# GPS-module.net
KiCad netlist of a schematic drawn in EAGLE
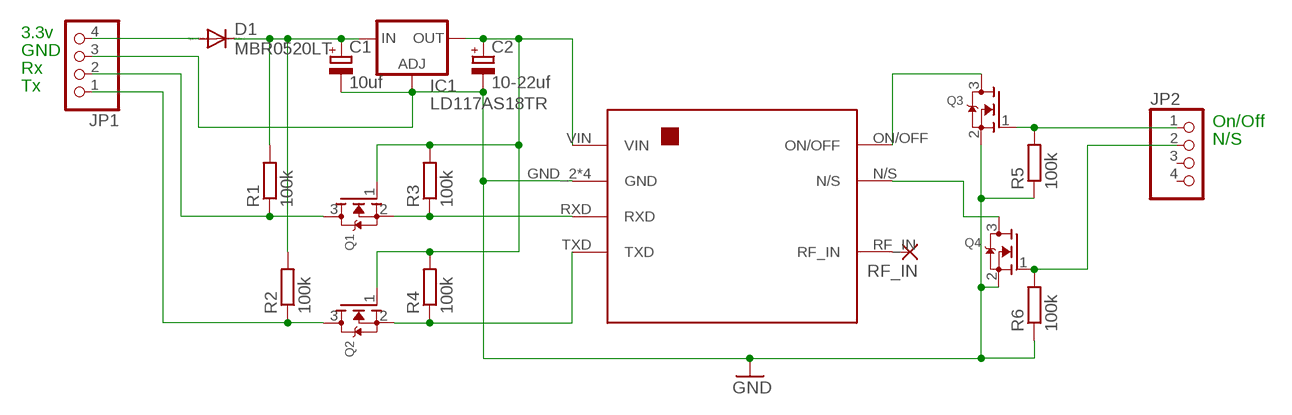
[diagram p0: schematic, sheet 1]

(export (version "E")
  (design (tool "Eeschema 10.0.6"))
  (components
    (comp (ref "C1")
      (value "10uf")
      (footprint "eagle-import:C_6032-28R")
      (libsource (lib "eagle-import") (part "CPOL-EUC/6032-28R"))
    )
    (comp (ref "C2")
      (value "10-22uf")
      (footprint "eagle-import:C_6032-28R")
      (libsource (lib "eagle-import") (part "CPOL-EUC/6032-28R"))
    )
    (comp (ref "D1")
      (value "MBR0520LT")
      (footprint "eagle-import:SOD123")
      (libsource (lib "eagle-import") (part "MBR0520LT"))
    )
    (comp (ref "IC1")
      (value "LD117AS18TR")
      (footprint "eagle-import:SOT223")
      (libsource (lib "eagle-import") (part "LD117A?S18TR"))
    )
    (comp (ref "JP1")
      (value "PINHD-1X4")
      (footprint "eagle-import:1X04")
      (libsource (lib "eagle-import") (part "PINHD-1X4"))
    )
    (comp (ref "JP2")
      (value "PINHD-1X4")
      (footprint "eagle-import:1X04")
      (libsource (lib "eagle-import") (part "PINHD-1X4"))
    )
    (comp (ref "Q1")
      (value "MOSFET-NREFLOW")
      (footprint "eagle-import:SOT23")
      (libsource (lib "eagle-import") (part "MOSFET-NREFLOW"))
    )
    (comp (ref "Q2")
      (value "MOSFET-NREFLOW")
      (footprint "eagle-import:SOT23")
      (libsource (lib "eagle-import") (part "MOSFET-NREFLOW"))
    )
    (comp (ref "Q3")
      (value "MOSFET-NREFLOW")
      (footprint "eagle-import:SOT23")
      (libsource (lib "eagle-import") (part "MOSFET-NREFLOW"))
    )
    (comp (ref "Q4")
      (value "MOSFET-NREFLOW")
      (footprint "eagle-import:SOT23")
      (libsource (lib "eagle-import") (part "MOSFET-NREFLOW"))
    )
    (comp (ref "R1")
      (value "100k")
      (footprint "eagle-import:M0805")
      (libsource (lib "eagle-import") (part "R-EU_M0805"))
    )
    (comp (ref "R2")
      (value "100k")
      (footprint "eagle-import:M0805")
      (libsource (lib "eagle-import") (part "R-EU_M0805"))
    )
    (comp (ref "R3")
      (value "100k")
      (footprint "eagle-import:M0805")
      (libsource (lib "eagle-import") (part "R-EU_M0805"))
    )
    (comp (ref "R4")
      (value "100k")
      (footprint "eagle-import:M0805")
      (libsource (lib "eagle-import") (part "R-EU_M0805"))
    )
    (comp (ref "R5")
      (value "100k")
      (footprint "eagle-import:M0805")
      (libsource (lib "eagle-import") (part "R-EU_M0805"))
    )
    (comp (ref "R6")
      (value "100k")
      (footprint "eagle-import:M0805")
      (libsource (lib "eagle-import") (part "R-EU_M0805"))
    )
    (comp (ref "RF_IN")
      (value "SMD2")
      (footprint "eagle-import:SMD1,27-2,54")
      (libsource (lib "eagle-import") (part "SMD2"))
    )
    (comp (ref "U$1")
      (value "GP4SF1109F2")
      (footprint "eagle-import:GP4SF1109F2")
      (libsource (lib "eagle-import") (part "GP4SF1109F2"))
    )
  )
  (nets
    (net (code "1") (name "GND") (class "Default")
      (node (ref "C1") (pin "-") (pinfunction "-_-") (pintype "passive"))
      (node (ref "C2") (pin "-") (pinfunction "-_-") (pintype "passive"))
      (node (ref "IC1") (pin "1") (pinfunction "ADJ_1") (pintype "input"))
      (node (ref "JP1") (pin "3") (pinfunction "3_3") (pintype "passive"))
      (node (ref "Q3") (pin "2") (pinfunction "S_2") (pintype "bidirectional"))
      (node (ref "Q4") (pin "2") (pinfunction "S_2") (pintype "bidirectional"))
      (node (ref "R5") (pin "1") (pinfunction "1_1") (pintype "passive"))
      (node (ref "R6") (pin "1") (pinfunction "1_1") (pintype "passive"))
      (node (ref "U$1") (pin "GND_2") (pinfunction "GND_GND_2") (pintype "bidirectional"))
      (node (ref "U$1") (pin "GND_5") (pinfunction "GND_GND_5") (pintype "bidirectional"))
      (node (ref "U$1") (pin "GND_6") (pinfunction "GND_GND_6") (pintype "bidirectional"))
      (node (ref "U$1") (pin "GND_8") (pinfunction "GND_GND_8") (pintype "bidirectional"))
    )
    (net (code "2") (name "Net-(D1-PadA)") (class "Default")
      (node (ref "D1") (pin "A") (pinfunction "A_A") (pintype "passive"))
      (node (ref "JP1") (pin "4") (pinfunction "4_4") (pintype "passive"))
    )
    (net (code "3") (name "Net-(IC1-IN)") (class "Default")
      (node (ref "C1") (pin "+") (pinfunction "+_+") (pintype "passive"))
      (node (ref "D1") (pin "C") (pinfunction "C_C") (pintype "passive"))
      (node (ref "IC1") (pin "3") (pinfunction "IN_3") (pintype "input"))
      (node (ref "R1") (pin "2") (pinfunction "2_2") (pintype "passive"))
      (node (ref "R2") (pin "2") (pinfunction "2_2") (pintype "passive"))
    )
    (net (code "4") (name "Net-(IC1-OUT)") (class "Default")
      (node (ref "C2") (pin "+") (pinfunction "+_+") (pintype "passive"))
      (node (ref "IC1") (pin "4") (pinfunction "OUT_4") (pintype "passive"))
      (node (ref "Q1") (pin "1") (pinfunction "G_1") (pintype "bidirectional"))
      (node (ref "Q2") (pin "1") (pinfunction "G_1") (pintype "bidirectional"))
      (node (ref "R3") (pin "2") (pinfunction "2_2") (pintype "passive"))
      (node (ref "R4") (pin "2") (pinfunction "2_2") (pintype "passive"))
      (node (ref "U$1") (pin "VIN") (pinfunction "VIN_VIN") (pintype "bidirectional"))
    )
    (net (code "5") (name "Net-(Q1-D)") (class "Default")
      (node (ref "JP1") (pin "2") (pinfunction "2_2") (pintype "passive"))
      (node (ref "Q1") (pin "3") (pinfunction "D_3") (pintype "bidirectional"))
      (node (ref "R1") (pin "1") (pinfunction "1_1") (pintype "passive"))
    )
    (net (code "6") (name "Net-(Q1-S)") (class "Default")
      (node (ref "Q1") (pin "2") (pinfunction "S_2") (pintype "bidirectional"))
      (node (ref "R3") (pin "1") (pinfunction "1_1") (pintype "passive"))
      (node (ref "U$1") (pin "RXD") (pinfunction "RXD_RXD") (pintype "bidirectional"))
    )
    (net (code "7") (name "Net-(Q2-D)") (class "Default")
      (node (ref "JP1") (pin "1") (pinfunction "1_1") (pintype "passive"))
      (node (ref "Q2") (pin "3") (pinfunction "D_3") (pintype "bidirectional"))
      (node (ref "R2") (pin "1") (pinfunction "1_1") (pintype "passive"))
    )
    (net (code "8") (name "Net-(Q2-S)") (class "Default")
      (node (ref "Q2") (pin "2") (pinfunction "S_2") (pintype "bidirectional"))
      (node (ref "R4") (pin "1") (pinfunction "1_1") (pintype "passive"))
      (node (ref "U$1") (pin "TXD") (pinfunction "TXD_TXD") (pintype "bidirectional"))
    )
    (net (code "9") (name "Net-(Q3-D)") (class "Default")
      (node (ref "Q3") (pin "3") (pinfunction "D_3") (pintype "bidirectional"))
      (node (ref "U$1") (pin "ON/OFF") (pinfunction "ON/OFF_ON/OFF") (pintype "bidirectional"))
    )
    (net (code "10") (name "Net-(Q3-G)") (class "Default")
      (node (ref "JP2") (pin "1") (pinfunction "1_1") (pintype "passive"))
      (node (ref "Q3") (pin "1") (pinfunction "G_1") (pintype "bidirectional"))
      (node (ref "R5") (pin "2") (pinfunction "2_2") (pintype "passive"))
    )
    (net (code "11") (name "Net-(Q4-D)") (class "Default")
      (node (ref "Q4") (pin "3") (pinfunction "D_3") (pintype "bidirectional"))
      (node (ref "U$1") (pin "N/S") (pinfunction "N/S_N/S") (pintype "bidirectional"))
    )
    (net (code "12") (name "Net-(Q4-G)") (class "Default")
      (node (ref "JP2") (pin "2") (pinfunction "2_2") (pintype "passive"))
      (node (ref "Q4") (pin "1") (pinfunction "G_1") (pintype "bidirectional"))
      (node (ref "R6") (pin "2") (pinfunction "2_2") (pintype "passive"))
    )
    (net (code "13") (name "Net-(RF_IN-P)") (class "Default")
      (node (ref "RF_IN") (pin "1") (pinfunction "P_1") (pintype "passive"))
      (node (ref "U$1") (pin "RF_IN") (pinfunction "RF_IN_RF_IN") (pintype "bidirectional"))
    )
    (net (code "14") (name "unconnected-(JP2-Pad3)") (class "Default")
      (node (ref "JP2") (pin "3") (pinfunction "3_3") (pintype "passive"))
    )
    (net (code "15") (name "unconnected-(JP2-Pad4)") (class "Default")
      (node (ref "JP2") (pin "4") (pinfunction "4_4") (pintype "passive"))
    )
  )
)
